# Sisyphus.net
KiCad netlist of a schematic drawn in EasyEDA Pro
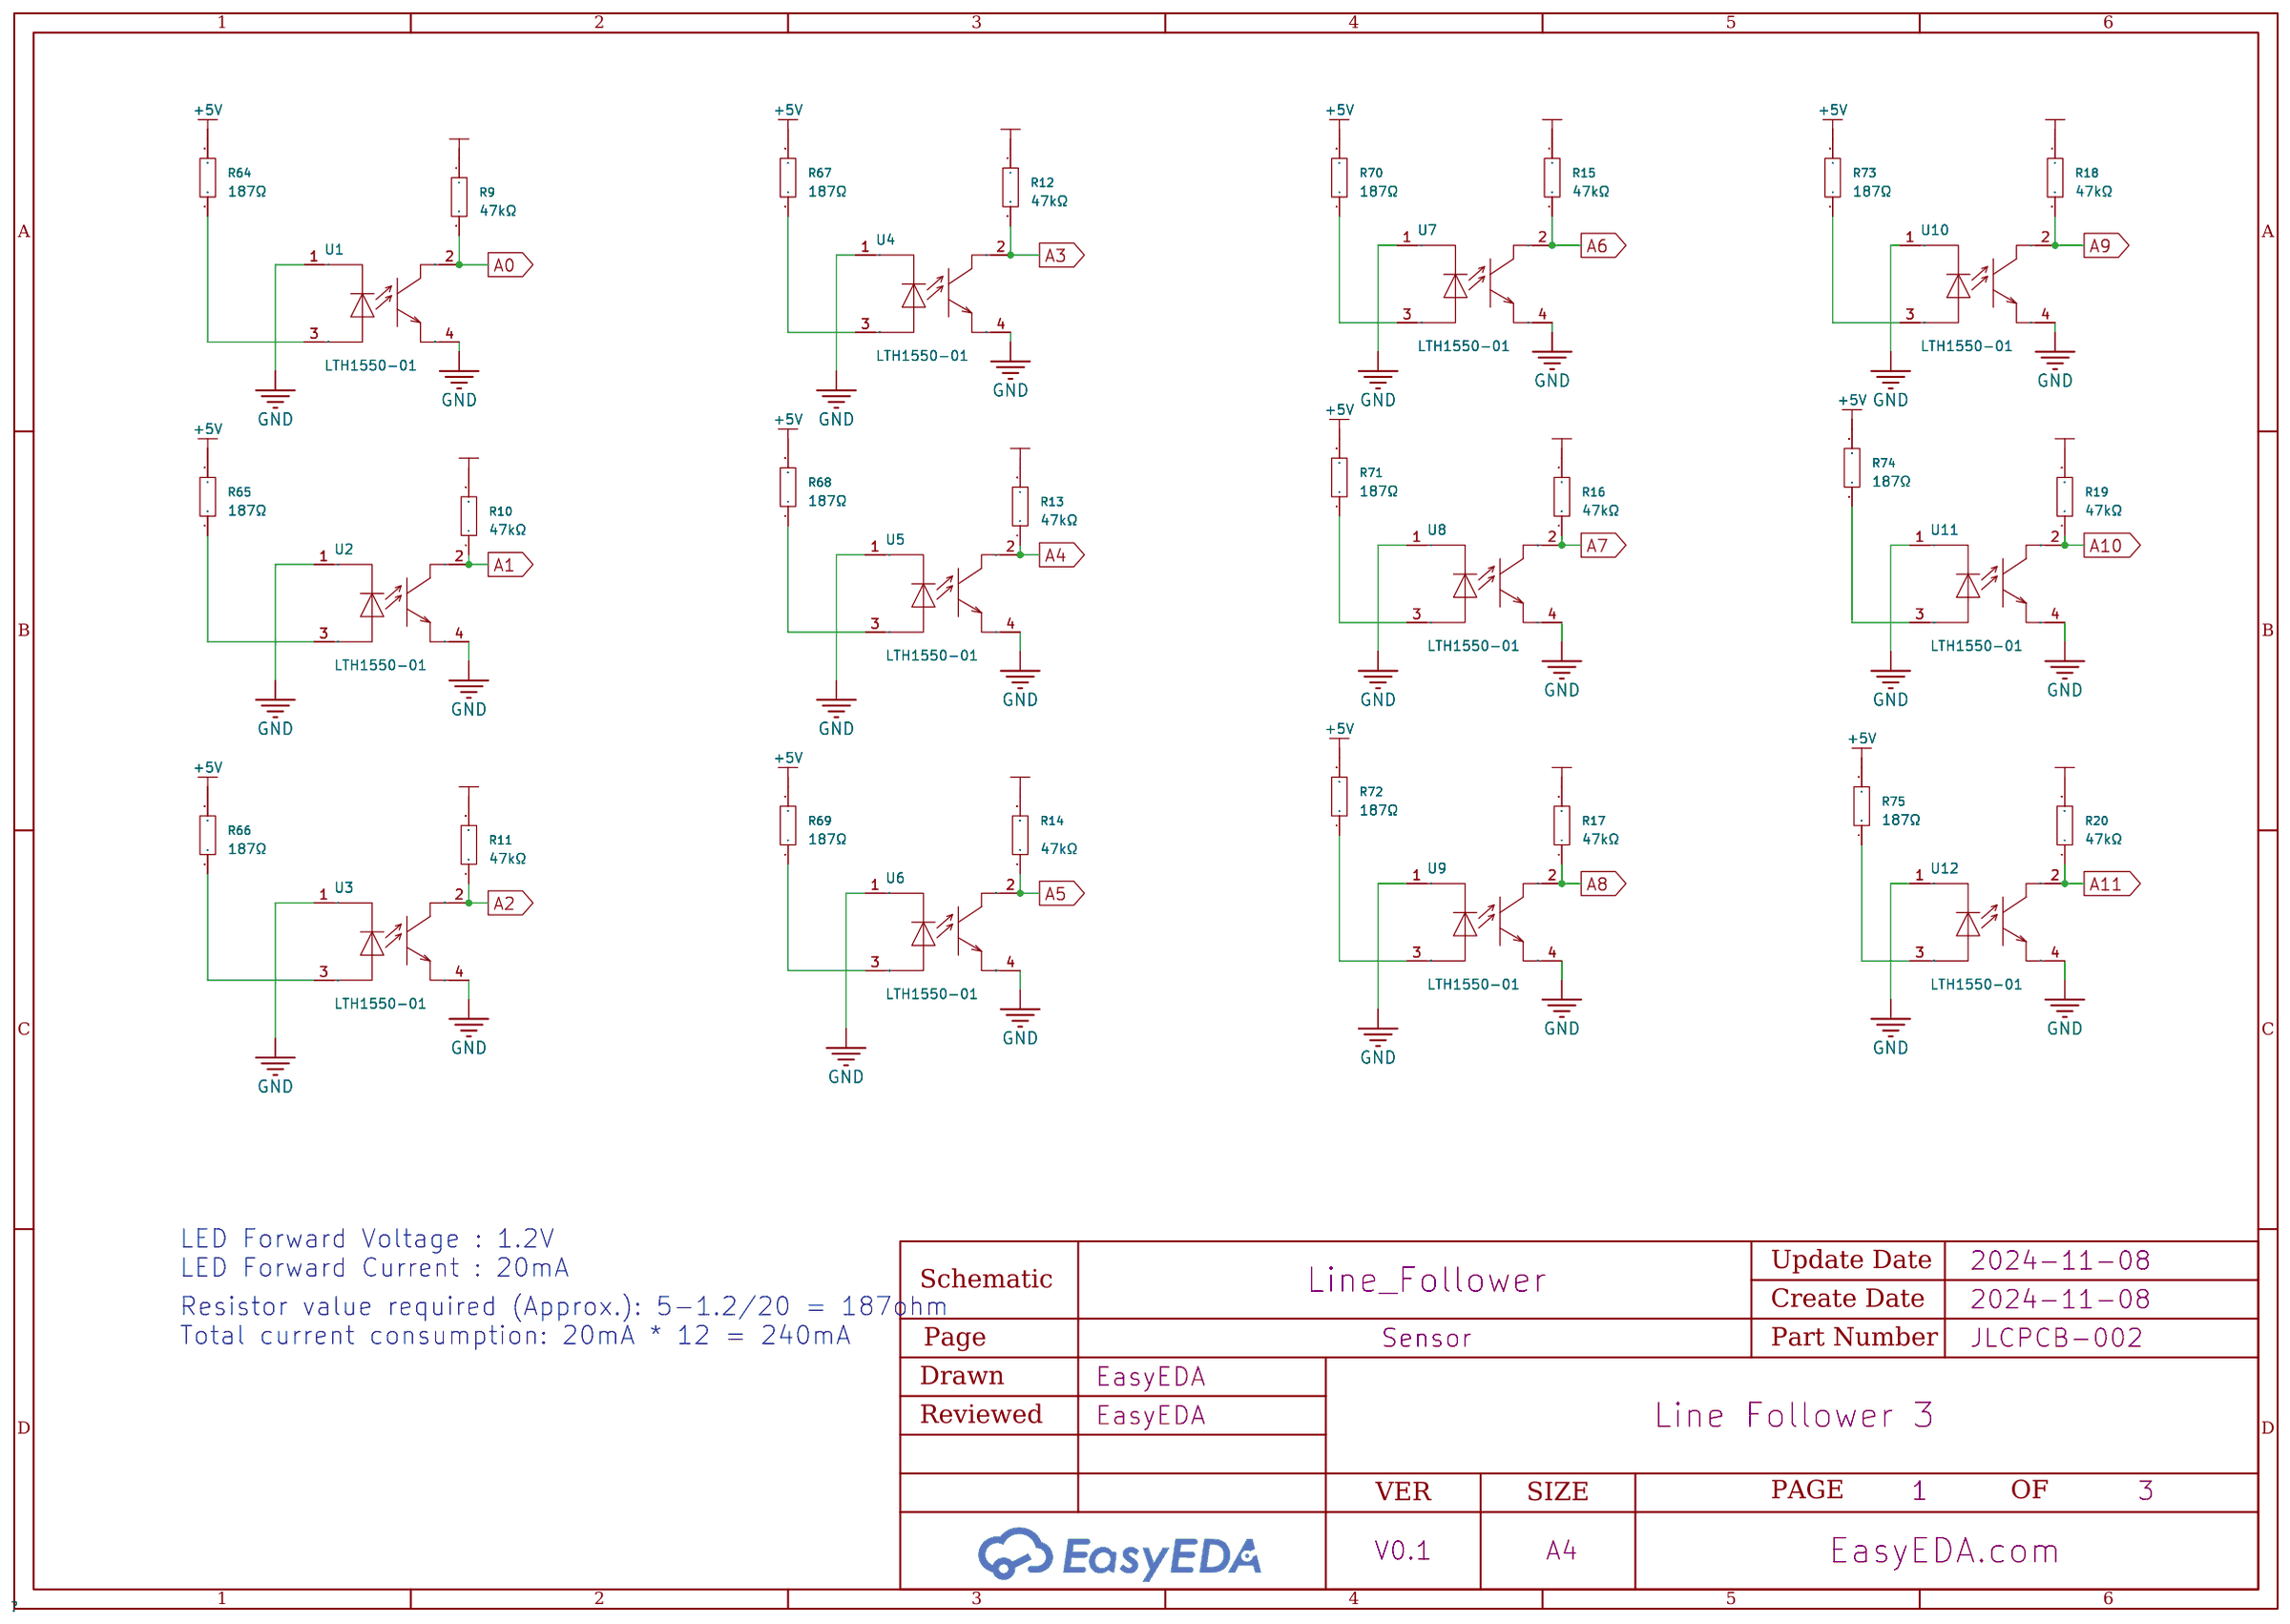
[diagram p0: Sensor]
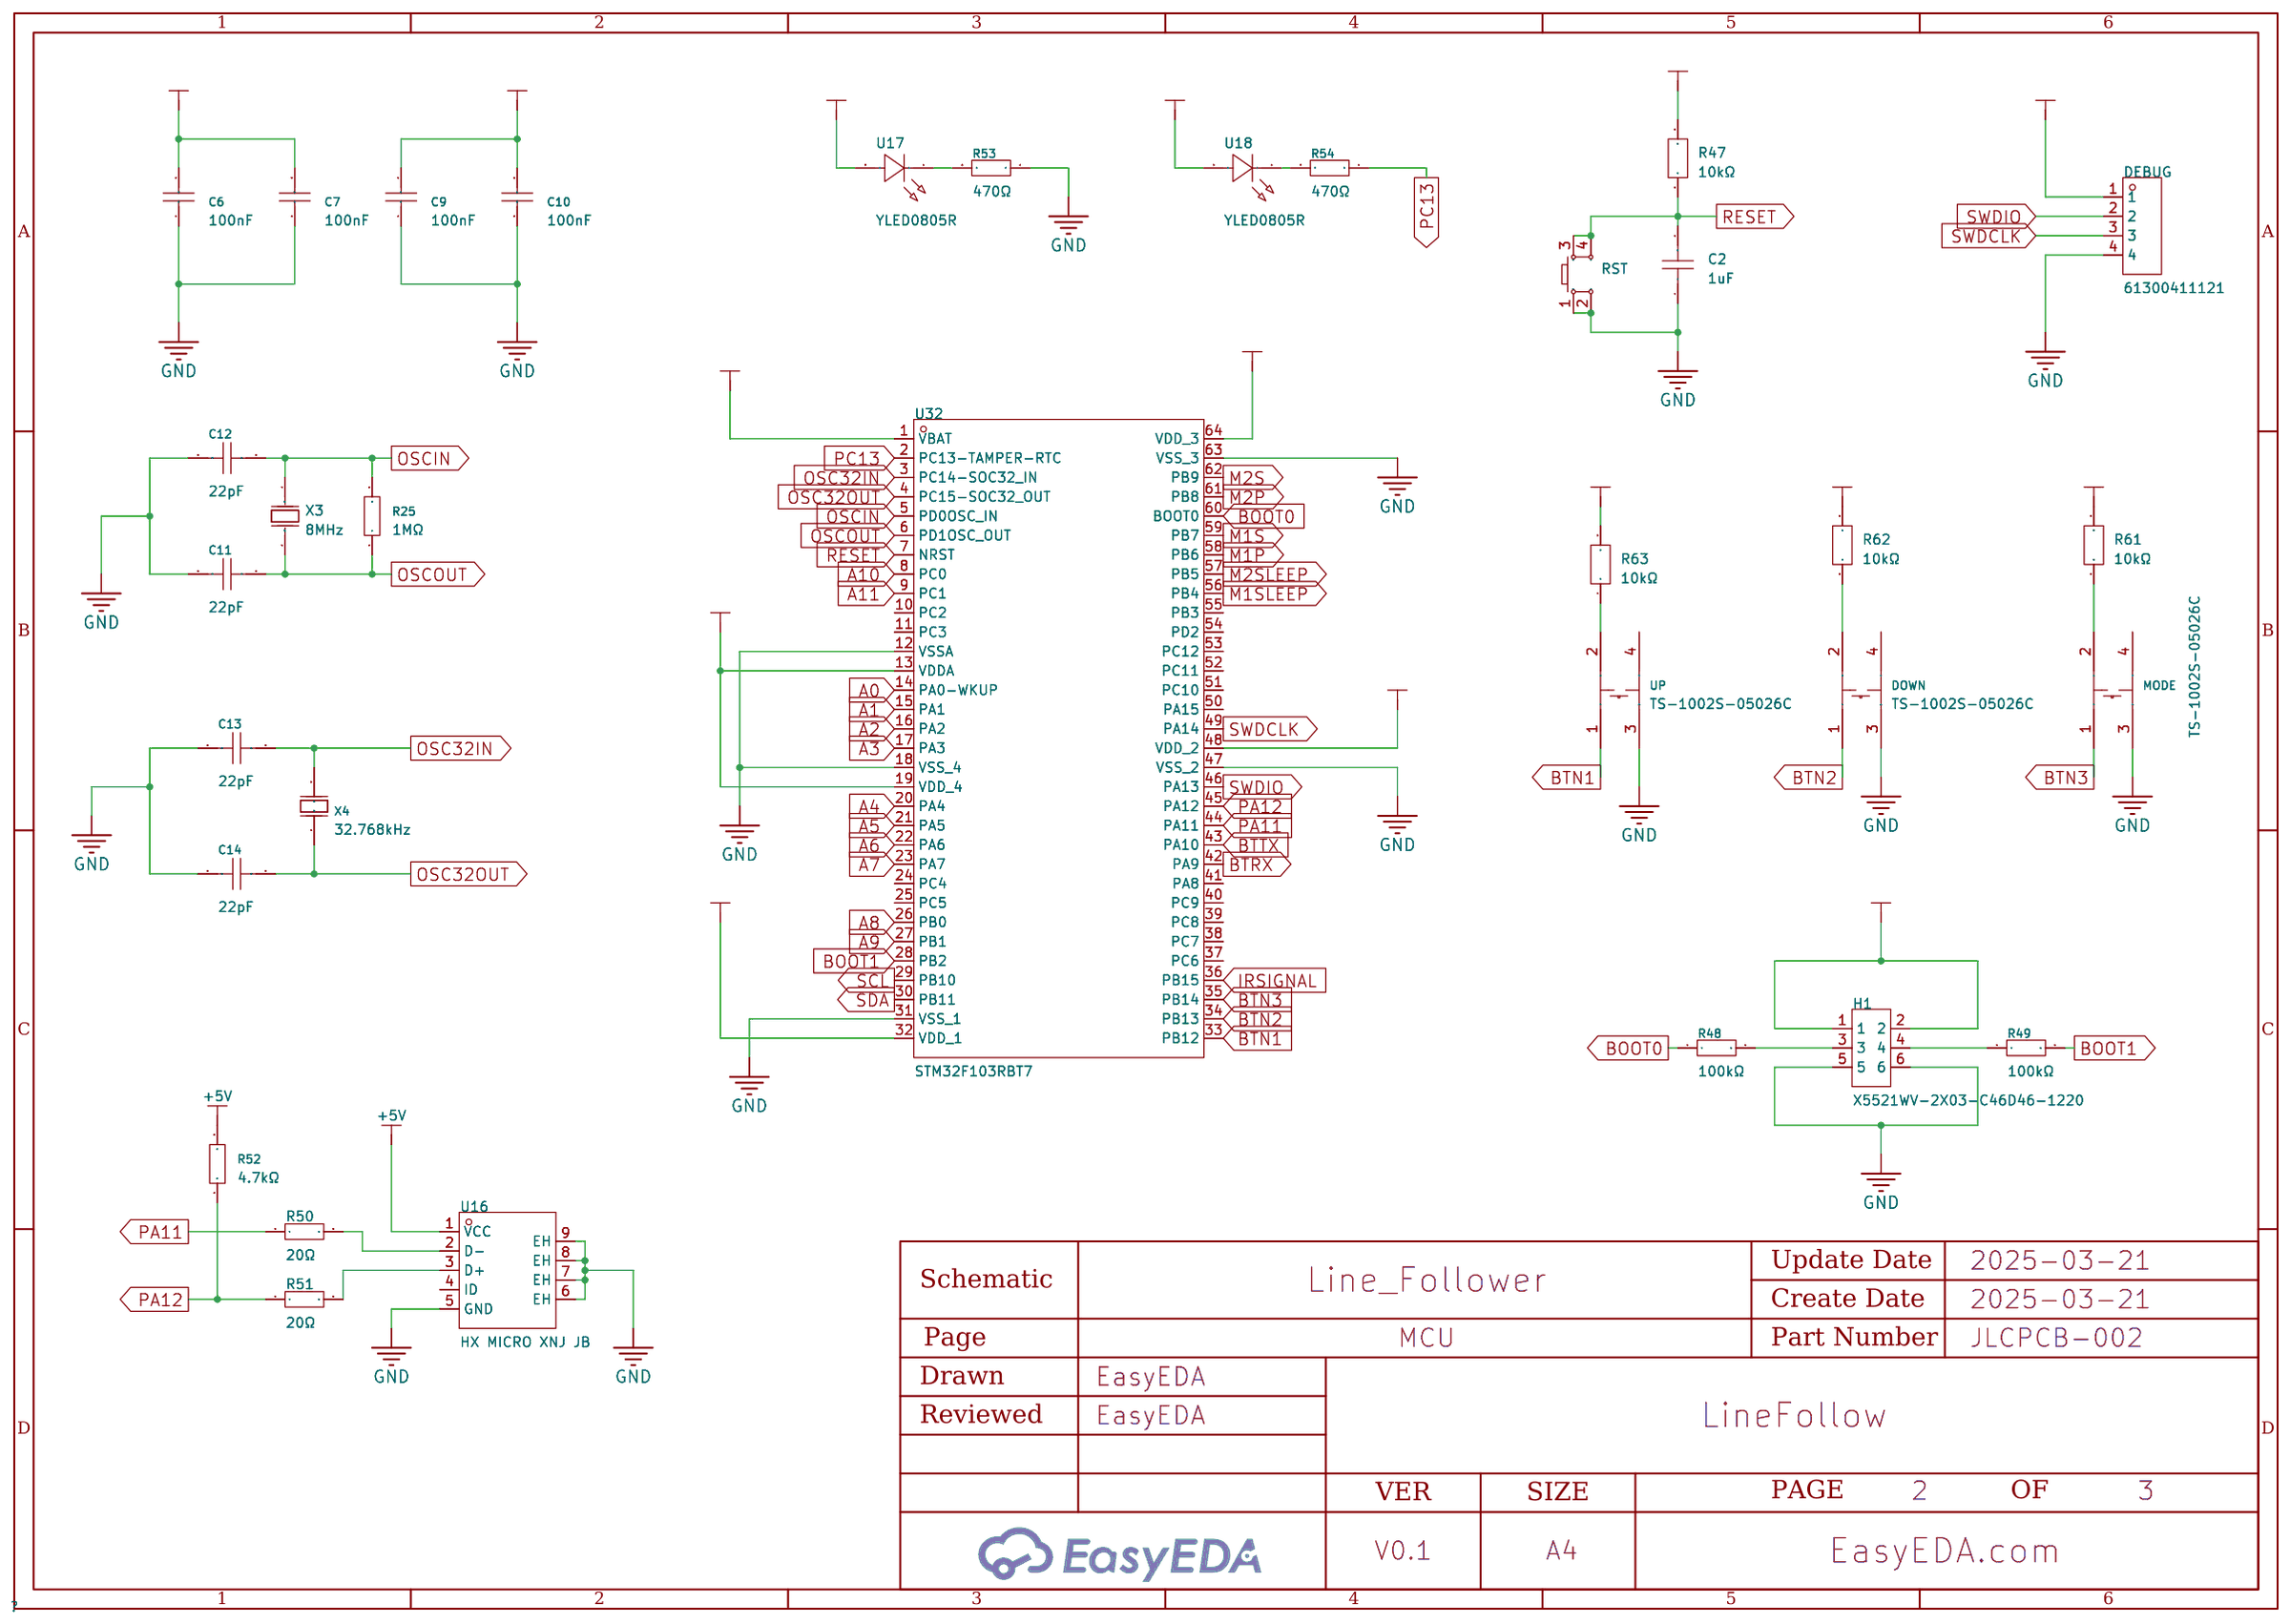
[diagram p1: MCU]
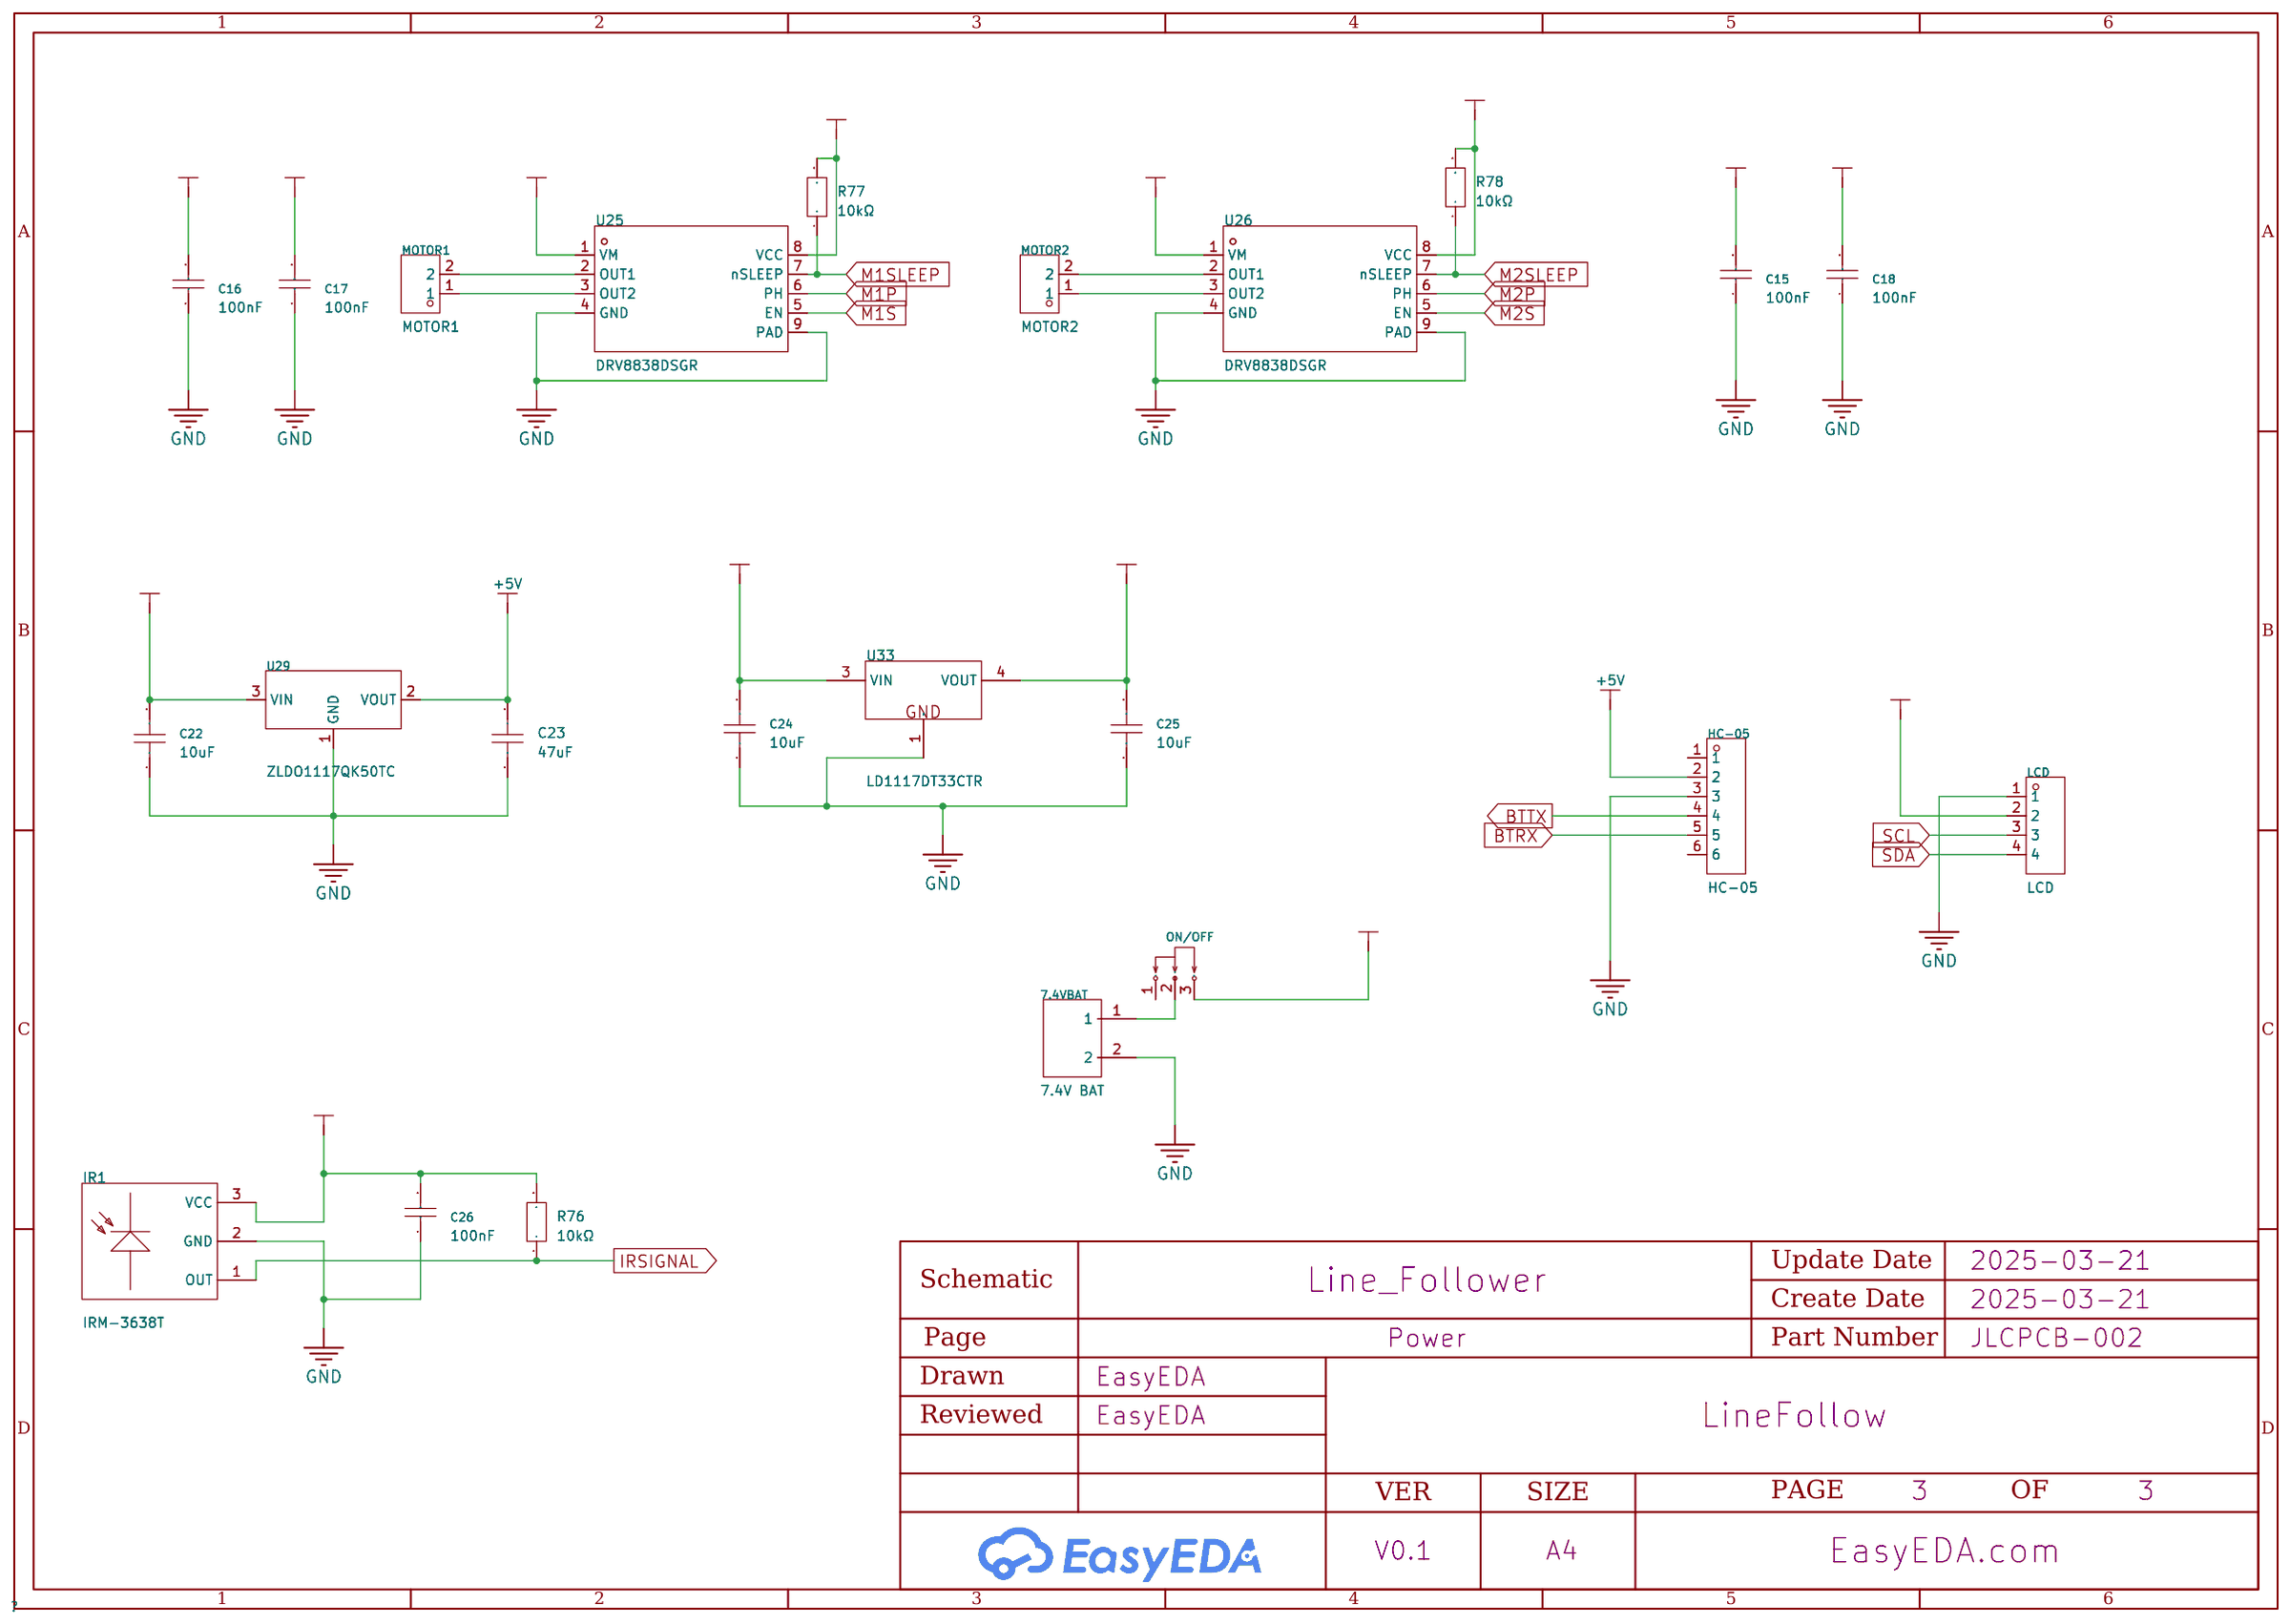
[diagram p2: Power]

(export (version "E")
  (design (tool "Eeschema 10.0.6"))
  (components
    (comp (ref "R9")
      (value "47kΩ")
      (footprint "easyedapro:R0805")
      (fields
        (field (name "Manufacturer Part") "0805W8F4702T5E")
        (field (name "Manufacturer") "UNI-ROYAL(厚声)")
      )
      (libsource (lib "easyedapro") (part "0805W8F4702T5E"))
    )
    (comp (ref "R10")
      (value "47kΩ")
      (footprint "easyedapro:R0805")
      (fields
        (field (name "Manufacturer Part") "0805W8F4702T5E")
        (field (name "Manufacturer") "UNI-ROYAL(厚声)")
      )
      (libsource (lib "easyedapro") (part "0805W8F4702T5E"))
    )
    (comp (ref "R11")
      (value "47kΩ")
      (footprint "easyedapro:R0805")
      (fields
        (field (name "Manufacturer Part") "0805W8F4702T5E")
        (field (name "Manufacturer") "UNI-ROYAL(厚声)")
      )
      (libsource (lib "easyedapro") (part "0805W8F4702T5E"))
    )
    (comp (ref "R12")
      (value "47kΩ")
      (footprint "easyedapro:R0805")
      (fields
        (field (name "Manufacturer Part") "0805W8F4702T5E")
        (field (name "Manufacturer") "UNI-ROYAL(厚声)")
      )
      (libsource (lib "easyedapro") (part "0805W8F4702T5E"))
    )
    (comp (ref "R13")
      (value "47kΩ")
      (footprint "easyedapro:R0805")
      (fields
        (field (name "Manufacturer Part") "0805W8F4702T5E")
        (field (name "Manufacturer") "UNI-ROYAL(厚声)")
      )
      (libsource (lib "easyedapro") (part "0805W8F4702T5E"))
    )
    (comp (ref "R14")
      (value "47kΩ")
      (footprint "easyedapro:R0805")
      (fields
        (field (name "Manufacturer Part") "0805W8F4702T5E")
        (field (name "Manufacturer") "UNI-ROYAL(厚声)")
      )
      (libsource (lib "easyedapro") (part "0805W8F4702T5E"))
    )
    (comp (ref "R15")
      (value "47kΩ")
      (footprint "easyedapro:R0805")
      (fields
        (field (name "Manufacturer Part") "0805W8F4702T5E")
        (field (name "Manufacturer") "UNI-ROYAL(厚声)")
      )
      (libsource (lib "easyedapro") (part "0805W8F4702T5E"))
    )
    (comp (ref "R16")
      (value "47kΩ")
      (footprint "easyedapro:R0805")
      (fields
        (field (name "Manufacturer Part") "0805W8F4702T5E")
        (field (name "Manufacturer") "UNI-ROYAL(厚声)")
      )
      (libsource (lib "easyedapro") (part "0805W8F4702T5E"))
    )
    (comp (ref "R17")
      (value "47kΩ")
      (footprint "easyedapro:R0805")
      (fields
        (field (name "Manufacturer Part") "0805W8F4702T5E")
        (field (name "Manufacturer") "UNI-ROYAL(厚声)")
      )
      (libsource (lib "easyedapro") (part "0805W8F4702T5E"))
    )
    (comp (ref "R18")
      (value "47kΩ")
      (footprint "easyedapro:R0805")
      (fields
        (field (name "Manufacturer Part") "0805W8F4702T5E")
        (field (name "Manufacturer") "UNI-ROYAL(厚声)")
      )
      (libsource (lib "easyedapro") (part "0805W8F4702T5E"))
    )
    (comp (ref "R19")
      (value "47kΩ")
      (footprint "easyedapro:R0805")
      (fields
        (field (name "Manufacturer Part") "0805W8F4702T5E")
        (field (name "Manufacturer") "UNI-ROYAL(厚声)")
      )
      (libsource (lib "easyedapro") (part "0805W8F4702T5E"))
    )
    (comp (ref "R20")
      (value "47kΩ")
      (footprint "easyedapro:R0805")
      (fields
        (field (name "Manufacturer Part") "0805W8F4702T5E")
        (field (name "Manufacturer") "UNI-ROYAL(厚声)")
      )
      (libsource (lib "easyedapro") (part "0805W8F4702T5E"))
    )
    (comp (ref "R64")
      (value "187Ω")
      (footprint "easyedapro:R0805")
      (fields (field (name "Manufacturer Part") "RTT051870FTP") (field (name "Manufacturer") "RALEC(旺诠)"))
      (libsource (lib "easyedapro") (part "RTT051870FTP"))
    )
    (comp (ref "R65")
      (value "187Ω")
      (footprint "easyedapro:R0805")
      (fields (field (name "Manufacturer Part") "RTT051870FTP") (field (name "Manufacturer") "RALEC(旺诠)"))
      (libsource (lib "easyedapro") (part "RTT051870FTP"))
    )
    (comp (ref "R66")
      (value "187Ω")
      (footprint "easyedapro:R0805")
      (fields (field (name "Manufacturer Part") "RTT051870FTP") (field (name "Manufacturer") "RALEC(旺诠)"))
      (libsource (lib "easyedapro") (part "RTT051870FTP"))
    )
    (comp (ref "R67")
      (value "187Ω")
      (footprint "easyedapro:R0805")
      (fields (field (name "Manufacturer Part") "RTT051870FTP") (field (name "Manufacturer") "RALEC(旺诠)"))
      (libsource (lib "easyedapro") (part "RTT051870FTP"))
    )
    (comp (ref "R68")
      (value "187Ω")
      (footprint "easyedapro:R0805")
      (fields (field (name "Manufacturer Part") "RTT051870FTP") (field (name "Manufacturer") "RALEC(旺诠)"))
      (libsource (lib "easyedapro") (part "RTT051870FTP"))
    )
    (comp (ref "R69")
      (value "187Ω")
      (footprint "easyedapro:R0805")
      (fields (field (name "Manufacturer Part") "RTT051870FTP") (field (name "Manufacturer") "RALEC(旺诠)"))
      (libsource (lib "easyedapro") (part "RTT051870FTP"))
    )
    (comp (ref "R70")
      (value "187Ω")
      (footprint "easyedapro:R0805")
      (fields (field (name "Manufacturer Part") "RTT051870FTP") (field (name "Manufacturer") "RALEC(旺诠)"))
      (libsource (lib "easyedapro") (part "RTT051870FTP"))
    )
    (comp (ref "R71")
      (value "187Ω")
      (footprint "easyedapro:R0805")
      (fields (field (name "Manufacturer Part") "RTT051870FTP") (field (name "Manufacturer") "RALEC(旺诠)"))
      (libsource (lib "easyedapro") (part "RTT051870FTP"))
    )
    (comp (ref "R72")
      (value "187Ω")
      (footprint "easyedapro:R0805")
      (fields (field (name "Manufacturer Part") "RTT051870FTP") (field (name "Manufacturer") "RALEC(旺诠)"))
      (libsource (lib "easyedapro") (part "RTT051870FTP"))
    )
    (comp (ref "R73")
      (value "187Ω")
      (footprint "easyedapro:R0805")
      (fields (field (name "Manufacturer Part") "RTT051870FTP") (field (name "Manufacturer") "RALEC(旺诠)"))
      (libsource (lib "easyedapro") (part "RTT051870FTP"))
    )
    (comp (ref "R74")
      (value "187Ω")
      (footprint "easyedapro:R0805")
      (fields (field (name "Manufacturer Part") "RTT051870FTP") (field (name "Manufacturer") "RALEC(旺诠)"))
      (libsource (lib "easyedapro") (part "RTT051870FTP"))
    )
    (comp (ref "R75")
      (value "187Ω")
      (footprint "easyedapro:R0805")
      (fields (field (name "Manufacturer Part") "RTT051870FTP") (field (name "Manufacturer") "RALEC(旺诠)"))
      (libsource (lib "easyedapro") (part "RTT051870FTP"))
    )
    (comp (ref "U1")
      (value "LTH1550-01")
      (footprint "easyedapro:OPTO-TH_4P-L8.7-W4.5-P4.10_LTH1550-01")
      (libsource (lib "easyedapro") (part "LTH1550-01"))
    )
    (comp (ref "U2")
      (value "LTH1550-01")
      (footprint "easyedapro:OPTO-TH_4P-L8.7-W4.5-P4.10_LTH1550-01")
      (libsource (lib "easyedapro") (part "LTH1550-01"))
    )
    (comp (ref "U3")
      (value "LTH1550-01")
      (footprint "easyedapro:OPTO-TH_4P-L8.7-W4.5-P4.10_LTH1550-01")
      (libsource (lib "easyedapro") (part "LTH1550-01"))
    )
    (comp (ref "U4")
      (value "LTH1550-01")
      (footprint "easyedapro:OPTO-TH_4P-L8.7-W4.5-P4.10_LTH1550-01")
      (libsource (lib "easyedapro") (part "LTH1550-01"))
    )
    (comp (ref "U5")
      (value "LTH1550-01")
      (footprint "easyedapro:OPTO-TH_4P-L8.7-W4.5-P4.10_LTH1550-01")
      (libsource (lib "easyedapro") (part "LTH1550-01"))
    )
    (comp (ref "U6")
      (value "LTH1550-01")
      (footprint "easyedapro:OPTO-TH_4P-L8.7-W4.5-P4.10_LTH1550-01")
      (libsource (lib "easyedapro") (part "LTH1550-01"))
    )
    (comp (ref "U7")
      (value "LTH1550-01")
      (footprint "easyedapro:OPTO-TH_4P-L8.7-W4.5-P4.10_LTH1550-01")
      (libsource (lib "easyedapro") (part "LTH1550-01"))
    )
    (comp (ref "U8")
      (value "LTH1550-01")
      (footprint "easyedapro:OPTO-TH_4P-L8.7-W4.5-P4.10_LTH1550-01")
      (libsource (lib "easyedapro") (part "LTH1550-01"))
    )
    (comp (ref "U9")
      (value "LTH1550-01")
      (footprint "easyedapro:OPTO-TH_4P-L8.7-W4.5-P4.10_LTH1550-01")
      (libsource (lib "easyedapro") (part "LTH1550-01"))
    )
    (comp (ref "U10")
      (value "LTH1550-01")
      (footprint "easyedapro:OPTO-TH_4P-L8.7-W4.5-P4.10_LTH1550-01")
      (libsource (lib "easyedapro") (part "LTH1550-01"))
    )
    (comp (ref "U11")
      (value "LTH1550-01")
      (footprint "easyedapro:OPTO-TH_4P-L8.7-W4.5-P4.10_LTH1550-01")
      (libsource (lib "easyedapro") (part "LTH1550-01"))
    )
    (comp (ref "U12")
      (value "LTH1550-01")
      (footprint "easyedapro:OPTO-TH_4P-L8.7-W4.5-P4.10_LTH1550-01")
      (libsource (lib "easyedapro") (part "LTH1550-01"))
    )
    (comp (ref "C2")
      (value "1uF")
      (footprint "easyedapro:C1206")
      (fields
        (field (name "Manufacturer Part") "CL31B105KBHNNNE")
        (field (name "Manufacturer") "SAMSUNG(三星)")
      )
      (libsource (lib "easyedapro") (part "CL31B105KBHNNNE"))
    )
    (comp (ref "C6")
      (value "100nF")
      (footprint "easyedapro:C1206")
      (fields
        (field (name "Manufacturer Part") "CL31B104KBCNNNC")
        (field (name "Manufacturer") "SAMSUNG(三星)")
      )
      (libsource (lib "easyedapro") (part "CL31B104KBCNNNC"))
    )
    (comp (ref "C7")
      (value "100nF")
      (footprint "easyedapro:C1206")
      (fields
        (field (name "Manufacturer Part") "CL31B104KBCNNNC")
        (field (name "Manufacturer") "SAMSUNG(三星)")
      )
      (libsource (lib "easyedapro") (part "CL31B104KBCNNNC"))
    )
    (comp (ref "C9")
      (value "100nF")
      (footprint "easyedapro:C1206")
      (fields
        (field (name "Manufacturer Part") "CL31B104KBCNNNC")
        (field (name "Manufacturer") "SAMSUNG(三星)")
      )
      (libsource (lib "easyedapro") (part "CL31B104KBCNNNC"))
    )
    (comp (ref "C10")
      (value "100nF")
      (footprint "easyedapro:C1206")
      (fields
        (field (name "Manufacturer Part") "CL31B104KBCNNNC")
        (field (name "Manufacturer") "SAMSUNG(三星)")
      )
      (libsource (lib "easyedapro") (part "CL31B104KBCNNNC"))
    )
    (comp (ref "C11")
      (value "22pF")
      (footprint "easyedapro:C0805")
      (fields
        (field (name "Manufacturer Part") "TCC0805COG220J500BT")
        (field (name "Manufacturer") "CCTC(三环)")
      )
      (libsource (lib "easyedapro") (part "TCC0805COG220J500BT"))
    )
    (comp (ref "C12")
      (value "22pF")
      (footprint "easyedapro:C0805")
      (fields
        (field (name "Manufacturer Part") "TCC0805COG220J500BT")
        (field (name "Manufacturer") "CCTC(三环)")
      )
      (libsource (lib "easyedapro") (part "TCC0805COG220J500BT"))
    )
    (comp (ref "C13")
      (value "22pF")
      (footprint "easyedapro:C0805")
      (fields
        (field (name "Manufacturer Part") "TCC0805COG220J500BT")
        (field (name "Manufacturer") "CCTC(三环)")
      )
      (libsource (lib "easyedapro") (part "TCC0805COG220J500BT"))
    )
    (comp (ref "C14")
      (value "22pF")
      (footprint "easyedapro:C0805")
      (fields
        (field (name "Manufacturer Part") "TCC0805COG220J500BT")
        (field (name "Manufacturer") "CCTC(三环)")
      )
      (libsource (lib "easyedapro") (part "TCC0805COG220J500BT"))
    )
    (comp (ref "DEBUG")
      (value "61300411121")
      (footprint "easyedapro:HDR-TH_4P-P2.54-V-M-1")
      (fields (field (name "Manufacturer") "Wurth(伍尔特)"))
      (libsource (lib "easyedapro") (part "61300411121"))
    )
    (comp (ref "DOWN")
      (value "TS-1002S-05026C")
      (footprint "easyedapro:KEY-SMD_4P-L6.0-W6.0-P4.50-LS9.0")
      (fields (field (name "Manufacturer") "XUNPU(讯普)"))
      (libsource (lib "easyedapro") (part "TS-1002S-05026C"))
    )
    (comp (ref "H1")
      (value "X5521WV-2X03-C46D46-1220")
      (footprint "easyedapro:HDR-TH_6P-P2.54-V-M-R2-C3-S2.54-3")
      (fields (field (name "Manufacturer") "XKB Connection(中国星坤)"))
      (libsource (lib "easyedapro") (part "X5521WV-2X03-C46D46-1220"))
    )
    (comp (ref "MODE")
      (value "TS-1002S-05026C")
      (footprint "easyedapro:KEY-SMD_4P-L6.0-W6.0-P4.50-LS9.0")
      (fields (field (name "Manufacturer") "XUNPU(讯普)"))
      (libsource (lib "easyedapro") (part "TS-1002S-05026C"))
    )
    (comp (ref "R25")
      (value "1MΩ")
      (footprint "easyedapro:R1206")
      (fields
        (field (name "Manufacturer Part") "1206W4F1004T5E")
        (field (name "Manufacturer") "UNI-ROYAL(厚声)")
      )
      (libsource (lib "easyedapro") (part "1206W4F1004T5E"))
    )
    (comp (ref "R47")
      (value "10kΩ")
      (footprint "easyedapro:R0805")
      (fields (field (name "Manufacturer Part") "FRC0805J103TS") (field (name "Manufacturer") "FOJAN(富捷)"))
      (libsource (lib "easyedapro") (part "FRC0805J103TS"))
    )
    (comp (ref "R48")
      (value "100kΩ")
      (footprint "easyedapro:R0805")
      (fields
        (field (name "Manufacturer Part") "0805W8F1003T5E")
        (field (name "Manufacturer") "UNI-ROYAL(厚声)")
      )
      (libsource (lib "easyedapro") (part "0805W8F1003T5E_C149504"))
    )
    (comp (ref "R49")
      (value "100kΩ")
      (footprint "easyedapro:R0805")
      (fields
        (field (name "Manufacturer Part") "0805W8F1003T5E")
        (field (name "Manufacturer") "UNI-ROYAL(厚声)")
      )
      (libsource (lib "easyedapro") (part "0805W8F1003T5E_C149504"))
    )
    (comp (ref "R50")
      (value "20Ω")
      (footprint "easyedapro:R0805")
      (fields (field (name "Manufacturer Part") "RS-05K20R0FT") (field (name "Manufacturer") "FH(风华)"))
      (libsource (lib "easyedapro") (part "RS-05K20R0FT"))
    )
    (comp (ref "R51")
      (value "20Ω")
      (footprint "easyedapro:R0805")
      (fields (field (name "Manufacturer Part") "RS-05K20R0FT") (field (name "Manufacturer") "FH(风华)"))
      (libsource (lib "easyedapro") (part "RS-05K20R0FT"))
    )
    (comp (ref "R52")
      (value "4.7kΩ")
      (footprint "easyedapro:R0805")
      (fields
        (field (name "Manufacturer Part") "0805W8F4701T5E")
        (field (name "Manufacturer") "UNI-ROYAL(厚声)")
      )
      (libsource (lib "easyedapro") (part "0805W8F4701T5E"))
    )
    (comp (ref "R53")
      (value "470Ω")
      (footprint "easyedapro:R0805")
      (fields
        (field (name "Manufacturer Part") "0805W8F4700T5E")
        (field (name "Manufacturer") "UNI-ROYAL(厚声)")
      )
      (libsource (lib "easyedapro") (part "0805W8F4700T5E"))
    )
    (comp (ref "R54")
      (value "470Ω")
      (footprint "easyedapro:R0805")
      (fields
        (field (name "Manufacturer Part") "0805W8F4700T5E")
        (field (name "Manufacturer") "UNI-ROYAL(厚声)")
      )
      (libsource (lib "easyedapro") (part "0805W8F4700T5E"))
    )
    (comp (ref "R61")
      (value "10kΩ")
      (footprint "easyedapro:R0805")
      (fields (field (name "Manufacturer Part") "FRC0805J103TS") (field (name "Manufacturer") "FOJAN(富捷)"))
      (libsource (lib "easyedapro") (part "FRC0805J103TS"))
    )
    (comp (ref "R62")
      (value "10kΩ")
      (footprint "easyedapro:R0805")
      (fields (field (name "Manufacturer Part") "FRC0805J103TS") (field (name "Manufacturer") "FOJAN(富捷)"))
      (libsource (lib "easyedapro") (part "FRC0805J103TS"))
    )
    (comp (ref "R63")
      (value "10kΩ")
      (footprint "easyedapro:R0805")
      (fields (field (name "Manufacturer Part") "FRC0805J103TS") (field (name "Manufacturer") "FOJAN(富捷)"))
      (libsource (lib "easyedapro") (part "FRC0805J103TS"))
    )
    (comp (ref "RST")
      (value "~")
      (footprint "easyedapro:SW-SMD_4P-L6.0-W6.0-P4.50-LS9.0-2")
      (libsource (lib "easyedapro") (part "轻触按键"))
    )
    (comp (ref "U16")
      (value "HX MICRO XNJ JB")
      (footprint "easyedapro:MICRO-USB-SMD_MICRONJ5P-1.0-1.25")
      (description "Connector Type:Micro-B Gender:Female")
      (fields (field (name "Manufacturer") "hanxia(韩下)"))
      (libsource (lib "easyedapro") (part "HX MICRO XNJ JB"))
    )
    (comp (ref "U17")
      (value "YLED0805R")
      (footprint "easyedapro:LED0805-RD")
      (fields (field (name "Manufacturer") "YONGYUTAI(永裕泰)"))
      (libsource (lib "easyedapro") (part "YLED0805R"))
    )
    (comp (ref "U18")
      (value "YLED0805R")
      (footprint "easyedapro:LED0805-RD")
      (fields (field (name "Manufacturer") "YONGYUTAI(永裕泰)"))
      (libsource (lib "easyedapro") (part "YLED0805R"))
    )
    (comp (ref "U32")
      (value "STM32F103RBT7")
      (footprint "easyedapro:LQFP-64_L10.0-W10.0-P0.50-LS12.0-BL")
      (fields (field (name "Manufacturer") "ST(意法半导体)"))
      (libsource (lib "easyedapro") (part "STM32F103RBT7"))
    )
    (comp (ref "UP")
      (value "TS-1002S-05026C")
      (footprint "easyedapro:KEY-SMD_4P-L6.0-W6.0-P4.50-LS9.0")
      (fields (field (name "Manufacturer") "XUNPU(讯普)"))
      (libsource (lib "easyedapro") (part "TS-1002S-05026C"))
    )
    (comp (ref "X3")
      (value "8MHz")
      (footprint "easyedapro:CRYSTAL-SMD_L11.5-W4.8-LS12.7")
      (fields (field (name "Manufacturer Part") "X49SM8MSD2SC") (field (name "Manufacturer") "YXC(扬兴晶振)"))
      (libsource (lib "easyedapro") (part "X49SM8MSD2SC"))
    )
    (comp (ref "X4")
      (value "32.768kHz")
      (footprint "easyedapro:OSC-SMD_2P-L3.2-W1.5")
      (fields (field (name "Manufacturer Part") "ABS07-32.768KHZ-T") (field (name "Manufacturer") "ABRACON"))
      (libsource (lib "easyedapro") (part "ABS07-32.768KHZ-T"))
    )
    (comp (ref "7.4VBAT")
      (value "7.4V BAT")
      (footprint "easyedapro:CONN-TH_WJ126V-5.0-2P")
      (fields (field (name "Manufacturer") "KANGNEX(康奈克斯电气)"))
      (libsource (lib "easyedapro") (part "WJ126V-5.0-2P"))
    )
    (comp (ref "C15")
      (value "100nF")
      (footprint "easyedapro:C1206")
      (fields
        (field (name "Manufacturer Part") "CL31B104KBCNNNC")
        (field (name "Manufacturer") "SAMSUNG(三星)")
      )
      (libsource (lib "easyedapro") (part "CL31B104KBCNNNC"))
    )
    (comp (ref "C16")
      (value "100nF")
      (footprint "easyedapro:C1206")
      (fields
        (field (name "Manufacturer Part") "CL31B104KBCNNNC")
        (field (name "Manufacturer") "SAMSUNG(三星)")
      )
      (libsource (lib "easyedapro") (part "CL31B104KBCNNNC"))
    )
    (comp (ref "C17")
      (value "100nF")
      (footprint "easyedapro:C1206")
      (fields
        (field (name "Manufacturer Part") "CL31B104KBCNNNC")
        (field (name "Manufacturer") "SAMSUNG(三星)")
      )
      (libsource (lib "easyedapro") (part "CL31B104KBCNNNC"))
    )
    (comp (ref "C18")
      (value "100nF")
      (footprint "easyedapro:C1206")
      (fields
        (field (name "Manufacturer Part") "CL31B104KBCNNNC")
        (field (name "Manufacturer") "SAMSUNG(三星)")
      )
      (libsource (lib "easyedapro") (part "CL31B104KBCNNNC"))
    )
    (comp (ref "C22")
      (value "10uF")
      (footprint "easyedapro:C0805")
      (fields
        (field (name "Manufacturer Part") "GRM21BR61E106KA73L")
        (field (name "Manufacturer") "muRata(村田)")
      )
      (libsource (lib "easyedapro") (part "GRM21BR61E106KA73L"))
    )
    (comp (ref "C23")
      (value "47uF")
      (footprint "easyedapro:C1206")
      (fields
        (field (name "Manufacturer Part") "GRM31CR61E476ME44L")
        (field (name "Manufacturer") "muRata(村田)")
      )
      (libsource (lib "easyedapro") (part "GRM31CR61E476ME44L"))
    )
    (comp (ref "C24")
      (value "10uF")
      (footprint "easyedapro:C0805")
      (fields
        (field (name "Manufacturer Part") "GRM21BR61E106KA73L")
        (field (name "Manufacturer") "muRata(村田)")
      )
      (libsource (lib "easyedapro") (part "GRM21BR61E106KA73L"))
    )
    (comp (ref "C25")
      (value "10uF")
      (footprint "easyedapro:C0805")
      (fields
        (field (name "Manufacturer Part") "GRM21BR61E106KA73L")
        (field (name "Manufacturer") "muRata(村田)")
      )
      (libsource (lib "easyedapro") (part "GRM21BR61E106KA73L"))
    )
    (comp (ref "C26")
      (value "100nF")
      (footprint "easyedapro:C1206")
      (fields
        (field (name "Manufacturer Part") "CL31B104KBCNNNC")
        (field (name "Manufacturer") "SAMSUNG(三星)")
      )
      (libsource (lib "easyedapro") (part "CL31B104KBCNNNC"))
    )
    (comp (ref "HC-05")
      (value "HC-05")
      (footprint "easyedapro:HDR-TH_6P-P2.54-V-F")
      (fields (field (name "Manufacturer") "BOOMELE(博穆精密)"))
      (libsource (lib "easyedapro") (part "Header-Female-2.54_1x6"))
    )
    (comp (ref "IR1")
      (value "IRM-3638T")
      (footprint "easyedapro:OPTO-TH_IRM-3638T")
      (fields (field (name "Manufacturer") "EVERLIGHT(亿光)"))
      (libsource (lib "easyedapro") (part "IRM-3638T"))
    )
    (comp (ref "LCD")
      (value "LCD")
      (footprint "easyedapro:HDR-TH_4P-P2.54-V-F")
      (fields (field (name "Manufacturer") "BOOMELE(博穆精密)"))
      (libsource (lib "easyedapro") (part "2.54-1*4P母"))
    )
    (comp (ref "MOTOR1")
      (value "MOTOR1")
      (footprint "easyedapro:HDR-TH_2P-P2.54-V-M")
      (fields (field (name "Manufacturer") "XFCN(兴飞)"))
      (libsource (lib "easyedapro") (part "PZ254V-11-02P"))
    )
    (comp (ref "MOTOR2")
      (value "MOTOR2")
      (footprint "easyedapro:HDR-TH_2P-P2.54-V-M")
      (fields (field (name "Manufacturer") "XFCN(兴飞)"))
      (libsource (lib "easyedapro") (part "PZ254V-11-02P"))
    )
    (comp (ref "ON/OFF")
      (value "SS12D10G4 071")
      (footprint "easyedapro:SW-TH_SHOU-HAN_SS12D10G4")
      (fields (field (name "Manufacturer") "SHOU HAN(首韩)"))
      (libsource (lib "easyedapro") (part "SS12D10G4 071"))
    )
    (comp (ref "R76")
      (value "10kΩ")
      (footprint "easyedapro:R0805")
      (fields (field (name "Manufacturer Part") "FRC0805J103TS") (field (name "Manufacturer") "FOJAN(富捷)"))
      (libsource (lib "easyedapro") (part "FRC0805J103TS"))
    )
    (comp (ref "R77")
      (value "10kΩ")
      (footprint "easyedapro:R0805")
      (fields (field (name "Manufacturer Part") "FRC0805J103TS") (field (name "Manufacturer") "FOJAN(富捷)"))
      (libsource (lib "easyedapro") (part "FRC0805J103TS"))
    )
    (comp (ref "R78")
      (value "10kΩ")
      (footprint "easyedapro:R0805")
      (fields (field (name "Manufacturer Part") "FRC0805J103TS") (field (name "Manufacturer") "FOJAN(富捷)"))
      (libsource (lib "easyedapro") (part "FRC0805J103TS"))
    )
    (comp (ref "U25")
      (value "DRV8838DSGR")
      (footprint "easyedapro:WSON-8_L2.0-W2.0-P0.50-TL-EP")
      (fields (field (name "Manufacturer") "TI(德州仪器)"))
      (libsource (lib "easyedapro") (part "DRV8838DSGR"))
    )
    (comp (ref "U26")
      (value "DRV8838DSGR")
      (footprint "easyedapro:WSON-8_L2.0-W2.0-P0.50-TL-EP")
      (fields (field (name "Manufacturer") "TI(德州仪器)"))
      (libsource (lib "easyedapro") (part "DRV8838DSGR"))
    )
    (comp (ref "U29")
      (value "ZLDO1117QK50TC")
      (footprint "easyedapro:TO-252-3_L6.6-W6.1-P4.57-LS9.9-BR-CW")
      (fields (field (name "Manufacturer") "DIODES(美台)"))
      (libsource (lib "easyedapro") (part "ZLDO1117QK50TC"))
    )
    (comp (ref "U33")
      (value "LD1117DT33CTR")
      (footprint "easyedapro:TO-252-2_L6.5-W6.1-P4.58-LS10.0-TL")
      (fields (field (name "Manufacturer") "ST(意法半导体)"))
      (libsource (lib "easyedapro") (part "LD1117DT33CTR"))
    )
  )
  (nets
    (net (code "1") (name "+3.3V") (class "Default")
      (node (ref "C10") (pin "2") (pinfunction "2_2") (pintype "input"))
      (node (ref "C17") (pin "2") (pinfunction "2_2") (pintype "input"))
      (node (ref "C18") (pin "2") (pinfunction "2_2") (pintype "input"))
      (node (ref "C25") (pin "2") (pinfunction "2_2") (pintype "input"))
      (node (ref "C26") (pin "2") (pinfunction "2_2") (pintype "input"))
      (node (ref "C6") (pin "2") (pinfunction "2_2") (pintype "input"))
      (node (ref "C7") (pin "2") (pinfunction "2_2") (pintype "input"))
      (node (ref "C9") (pin "2") (pinfunction "2_2") (pintype "input"))
      (node (ref "DEBUG") (pin "1") (pinfunction "1_1") (pintype "unspecified"))
      (node (ref "H1") (pin "1") (pinfunction "1_1") (pintype "unspecified"))
      (node (ref "H1") (pin "2") (pinfunction "2_2") (pintype "unspecified"))
      (node (ref "IR1") (pin "3") (pinfunction "VCC_3") (pintype "input"))
      (node (ref "LCD") (pin "2") (pinfunction "2_2") (pintype "input"))
      (node (ref "R10") (pin "2") (pinfunction "2_2") (pintype "input"))
      (node (ref "R11") (pin "2") (pinfunction "2_2") (pintype "input"))
      (node (ref "R12") (pin "1") (pinfunction "1_1") (pintype "input"))
      (node (ref "R13") (pin "2") (pinfunction "2_2") (pintype "input"))
      (node (ref "R14") (pin "2") (pinfunction "2_2") (pintype "input"))
      (node (ref "R15") (pin "1") (pinfunction "1_1") (pintype "input"))
      (node (ref "R16") (pin "2") (pinfunction "2_2") (pintype "input"))
      (node (ref "R17") (pin "2") (pinfunction "2_2") (pintype "input"))
      (node (ref "R18") (pin "1") (pinfunction "1_1") (pintype "input"))
      (node (ref "R19") (pin "2") (pinfunction "2_2") (pintype "input"))
      (node (ref "R20") (pin "2") (pinfunction "2_2") (pintype "input"))
      (node (ref "R47") (pin "2") (pinfunction "2_2") (pintype "unspecified"))
      (node (ref "R61") (pin "2") (pinfunction "2_2") (pintype "unspecified"))
      (node (ref "R62") (pin "1") (pinfunction "1_1") (pintype "unspecified"))
      (node (ref "R63") (pin "2") (pinfunction "2_2") (pintype "unspecified"))
      (node (ref "R76") (pin "2") (pinfunction "2_2") (pintype "unspecified"))
      (node (ref "R77") (pin "2") (pinfunction "2_2") (pintype "unspecified"))
      (node (ref "R78") (pin "2") (pinfunction "2_2") (pintype "unspecified"))
      (node (ref "R9") (pin "1") (pinfunction "1_1") (pintype "input"))
      (node (ref "U17") (pin "2") (pinfunction "A_2") (pintype "unspecified"))
      (node (ref "U18") (pin "2") (pinfunction "A_2") (pintype "unspecified"))
      (node (ref "U25") (pin "8") (pinfunction "VCC_8") (pintype "unspecified"))
      (node (ref "U26") (pin "8") (pinfunction "VCC_8") (pintype "unspecified"))
      (node (ref "U32") (pin "1") (pinfunction "VBAT_1") (pintype "unspecified"))
      (node (ref "U32") (pin "13") (pinfunction "VDDA_13") (pintype "unspecified"))
      (node (ref "U32") (pin "19") (pinfunction "VDD_4_19") (pintype "unspecified"))
      (node (ref "U32") (pin "32") (pinfunction "VDD_1_32") (pintype "unspecified"))
      (node (ref "U32") (pin "48") (pinfunction "VDD_2_48") (pintype "unspecified"))
      (node (ref "U32") (pin "64") (pinfunction "VDD_3_64") (pintype "unspecified"))
      (node (ref "U33") (pin "4") (pinfunction "VOUT_4") (pintype "unspecified"))
    )
    (net (code "2") (name "+5V") (class "Default")
      (node (ref "C23") (pin "2") (pinfunction "2_2") (pintype "unspecified"))
      (node (ref "HC-05") (pin "2") (pinfunction "2_2") (pintype "input"))
      (node (ref "R52") (pin "2") (pinfunction "2_2") (pintype "input"))
      (node (ref "R64") (pin "2") (pinfunction "2_2") (pintype "input"))
      (node (ref "R65") (pin "2") (pinfunction "2_2") (pintype "input"))
      (node (ref "R66") (pin "2") (pinfunction "2_2") (pintype "input"))
      (node (ref "R67") (pin "2") (pinfunction "2_2") (pintype "input"))
      (node (ref "R68") (pin "2") (pinfunction "2_2") (pintype "input"))
      (node (ref "R69") (pin "2") (pinfunction "2_2") (pintype "input"))
      (node (ref "R70") (pin "2") (pinfunction "2_2") (pintype "input"))
      (node (ref "R71") (pin "2") (pinfunction "2_2") (pintype "input"))
      (node (ref "R72") (pin "2") (pinfunction "2_2") (pintype "input"))
      (node (ref "R73") (pin "2") (pinfunction "2_2") (pintype "input"))
      (node (ref "R74") (pin "2") (pinfunction "2_2") (pintype "input"))
      (node (ref "R75") (pin "2") (pinfunction "2_2") (pintype "input"))
      (node (ref "U16") (pin "1") (pinfunction "VCC_1") (pintype "unspecified"))
      (node (ref "U29") (pin "2") (pinfunction "VOUT_2") (pintype "input"))
    )
    (net (code "3") (name "+7.4V") (class "Default")
      (node (ref "C15") (pin "2") (pinfunction "2_2") (pintype "input"))
      (node (ref "C16") (pin "2") (pinfunction "2_2") (pintype "input"))
      (node (ref "C22") (pin "2") (pinfunction "2_2") (pintype "input"))
      (node (ref "C24") (pin "2") (pinfunction "2_2") (pintype "input"))
      (node (ref "ON/OFF") (pin "3") (pinfunction "3_3") (pintype "input"))
      (node (ref "U25") (pin "1") (pinfunction "VM_1") (pintype "unspecified"))
      (node (ref "U26") (pin "1") (pinfunction "VM_1") (pintype "unspecified"))
      (node (ref "U29") (pin "3") (pinfunction "VIN_3") (pintype "input"))
      (node (ref "U33") (pin "3") (pinfunction "VIN_3") (pintype "unspecified"))
    )
    (net (code "4") (name "A0") (class "Default")
      (node (ref "R9") (pin "2") (pinfunction "2_2") (pintype "input"))
      (node (ref "U1") (pin "2") (pinfunction "C_2") (pintype "unspecified"))
      (node (ref "U32") (pin "14") (pinfunction "PA0-WKUP_14") (pintype "unspecified"))
    )
    (net (code "5") (name "A1") (class "Default")
      (node (ref "R10") (pin "1") (pinfunction "1_1") (pintype "input"))
      (node (ref "U2") (pin "2") (pinfunction "C_2") (pintype "unspecified"))
      (node (ref "U32") (pin "15") (pinfunction "PA1_15") (pintype "unspecified"))
    )
    (net (code "6") (name "A2") (class "Default")
      (node (ref "R11") (pin "1") (pinfunction "1_1") (pintype "input"))
      (node (ref "U3") (pin "2") (pinfunction "C_2") (pintype "unspecified"))
      (node (ref "U32") (pin "16") (pinfunction "PA2_16") (pintype "unspecified"))
    )
    (net (code "7") (name "A3") (class "Default")
      (node (ref "R12") (pin "2") (pinfunction "2_2") (pintype "input"))
      (node (ref "U32") (pin "17") (pinfunction "PA3_17") (pintype "unspecified"))
      (node (ref "U4") (pin "2") (pinfunction "C_2") (pintype "unspecified"))
    )
    (net (code "8") (name "A4") (class "Default")
      (node (ref "R13") (pin "1") (pinfunction "1_1") (pintype "input"))
      (node (ref "U32") (pin "20") (pinfunction "PA4_20") (pintype "unspecified"))
      (node (ref "U5") (pin "2") (pinfunction "C_2") (pintype "unspecified"))
    )
    (net (code "9") (name "A5") (class "Default")
      (node (ref "R14") (pin "1") (pinfunction "1_1") (pintype "input"))
      (node (ref "U32") (pin "21") (pinfunction "PA5_21") (pintype "unspecified"))
      (node (ref "U6") (pin "2") (pinfunction "C_2") (pintype "unspecified"))
    )
    (net (code "10") (name "A6") (class "Default")
      (node (ref "R15") (pin "2") (pinfunction "2_2") (pintype "input"))
      (node (ref "U32") (pin "22") (pinfunction "PA6_22") (pintype "unspecified"))
      (node (ref "U7") (pin "2") (pinfunction "C_2") (pintype "unspecified"))
    )
    (net (code "11") (name "A7") (class "Default")
      (node (ref "R16") (pin "1") (pinfunction "1_1") (pintype "input"))
      (node (ref "U32") (pin "23") (pinfunction "PA7_23") (pintype "unspecified"))
      (node (ref "U8") (pin "2") (pinfunction "C_2") (pintype "unspecified"))
    )
    (net (code "12") (name "A8") (class "Default")
      (node (ref "R17") (pin "1") (pinfunction "1_1") (pintype "input"))
      (node (ref "U32") (pin "26") (pinfunction "PB0_26") (pintype "unspecified"))
      (node (ref "U9") (pin "2") (pinfunction "C_2") (pintype "unspecified"))
    )
    (net (code "13") (name "A9") (class "Default")
      (node (ref "R18") (pin "2") (pinfunction "2_2") (pintype "input"))
      (node (ref "U10") (pin "2") (pinfunction "C_2") (pintype "unspecified"))
      (node (ref "U32") (pin "27") (pinfunction "PB1_27") (pintype "unspecified"))
    )
    (net (code "14") (name "A10") (class "Default")
      (node (ref "R19") (pin "1") (pinfunction "1_1") (pintype "input"))
      (node (ref "U11") (pin "2") (pinfunction "C_2") (pintype "unspecified"))
      (node (ref "U32") (pin "8") (pinfunction "PC0_8") (pintype "unspecified"))
    )
    (net (code "15") (name "A11") (class "Default")
      (node (ref "R20") (pin "1") (pinfunction "1_1") (pintype "input"))
      (node (ref "U12") (pin "2") (pinfunction "C_2") (pintype "unspecified"))
      (node (ref "U32") (pin "9") (pinfunction "PC1_9") (pintype "unspecified"))
    )
    (net (code "16") (name "BOOT0") (class "Default")
      (node (ref "R48") (pin "1") (pinfunction "1_1") (pintype "input"))
      (node (ref "U32") (pin "60") (pinfunction "BOOT0_60") (pintype "unspecified"))
    )
    (net (code "17") (name "BOOT1") (class "Default")
      (node (ref "R49") (pin "2") (pinfunction "2_2") (pintype "input"))
      (node (ref "U32") (pin "28") (pinfunction "PB2_28") (pintype "unspecified"))
    )
    (net (code "18") (name "BTN1") (class "Default")
      (node (ref "U32") (pin "33") (pinfunction "PB12_33") (pintype "unspecified"))
      (node (ref "UP") (pin "1") (pinfunction "1_1") (pintype "input"))
    )
    (net (code "19") (name "BTN2") (class "Default")
      (node (ref "DOWN") (pin "1") (pinfunction "1_1") (pintype "input"))
      (node (ref "U32") (pin "34") (pinfunction "PB13_34") (pintype "unspecified"))
    )
    (net (code "20") (name "BTN3") (class "Default")
      (node (ref "MODE") (pin "1") (pinfunction "1_1") (pintype "input"))
      (node (ref "U32") (pin "35") (pinfunction "PB14_35") (pintype "unspecified"))
    )
    (net (code "21") (name "BTRX") (class "Default")
      (node (ref "HC-05") (pin "5") (pinfunction "5_5") (pintype "input"))
      (node (ref "U32") (pin "42") (pinfunction "PA9_42") (pintype "unspecified"))
    )
    (net (code "22") (name "BTTX") (class "Default")
      (node (ref "HC-05") (pin "4") (pinfunction "4_4") (pintype "input"))
      (node (ref "U32") (pin "43") (pinfunction "PA10_43") (pintype "unspecified"))
    )
    (net (code "23") (name "GND") (class "Default")
      (node (ref "7.4VBAT") (pin "2") (pinfunction "2_2") (pintype "input"))
      (node (ref "C10") (pin "1") (pinfunction "1_1") (pintype "input"))
      (node (ref "C11") (pin "2") (pinfunction "2_2") (pintype "input"))
      (node (ref "C12") (pin "2") (pinfunction "2_2") (pintype "input"))
      (node (ref "C13") (pin "2") (pinfunction "2_2") (pintype "input"))
      (node (ref "C14") (pin "2") (pinfunction "2_2") (pintype "input"))
      (node (ref "C15") (pin "1") (pinfunction "1_1") (pintype "input"))
      (node (ref "C16") (pin "1") (pinfunction "1_1") (pintype "input"))
      (node (ref "C17") (pin "1") (pinfunction "1_1") (pintype "input"))
      (node (ref "C18") (pin "1") (pinfunction "1_1") (pintype "input"))
      (node (ref "C2") (pin "1") (pinfunction "1_1") (pintype "unspecified"))
      (node (ref "C22") (pin "1") (pinfunction "1_1") (pintype "input"))
      (node (ref "C23") (pin "1") (pinfunction "1_1") (pintype "unspecified"))
      (node (ref "C24") (pin "1") (pinfunction "1_1") (pintype "input"))
      (node (ref "C25") (pin "1") (pinfunction "1_1") (pintype "input"))
      (node (ref "C26") (pin "1") (pinfunction "1_1") (pintype "input"))
      (node (ref "C6") (pin "1") (pinfunction "1_1") (pintype "input"))
      (node (ref "C7") (pin "1") (pinfunction "1_1") (pintype "input"))
      (node (ref "C9") (pin "1") (pinfunction "1_1") (pintype "input"))
      (node (ref "DEBUG") (pin "4") (pinfunction "4_4") (pintype "unspecified"))
      (node (ref "DOWN") (pin "3") (pinfunction "3_3") (pintype "input"))
      (node (ref "H1") (pin "5") (pinfunction "5_5") (pintype "unspecified"))
      (node (ref "H1") (pin "6") (pinfunction "6_6") (pintype "unspecified"))
      (node (ref "HC-05") (pin "3") (pinfunction "3_3") (pintype "input"))
      (node (ref "IR1") (pin "2") (pinfunction "GND_2") (pintype "input"))
      (node (ref "LCD") (pin "1") (pinfunction "1_1") (pintype "input"))
      (node (ref "MODE") (pin "3") (pinfunction "3_3") (pintype "input"))
      (node (ref "R53") (pin "1") (pinfunction "1_1") (pintype "input"))
      (node (ref "RST") (pin "1") (pinfunction "1_1") (pintype "input"))
      (node (ref "RST") (pin "2") (pinfunction "2_2") (pintype "input"))
      (node (ref "U1") (pin "1") (pinfunction "A_1") (pintype "unspecified"))
      (node (ref "U1") (pin "4") (pinfunction "EM_4") (pintype "unspecified"))
      (node (ref "U10") (pin "1") (pinfunction "A_1") (pintype "unspecified"))
      (node (ref "U10") (pin "4") (pinfunction "EM_4") (pintype "unspecified"))
      (node (ref "U11") (pin "1") (pinfunction "A_1") (pintype "unspecified"))
      (node (ref "U11") (pin "4") (pinfunction "EM_4") (pintype "unspecified"))
      (node (ref "U12") (pin "1") (pinfunction "A_1") (pintype "unspecified"))
      (node (ref "U12") (pin "4") (pinfunction "EM_4") (pintype "unspecified"))
      (node (ref "U16") (pin "5") (pinfunction "GND_5") (pintype "unspecified"))
      (node (ref "U16") (pin "6") (pinfunction "EH_6") (pintype "unspecified"))
      (node (ref "U16") (pin "7") (pinfunction "EH_7") (pintype "unspecified"))
      (node (ref "U16") (pin "8") (pinfunction "EH_8") (pintype "unspecified"))
      (node (ref "U16") (pin "9") (pinfunction "EH_9") (pintype "unspecified"))
      (node (ref "U2") (pin "1") (pinfunction "A_1") (pintype "unspecified"))
      (node (ref "U2") (pin "4") (pinfunction "EM_4") (pintype "unspecified"))
      (node (ref "U25") (pin "4") (pinfunction "GND_4") (pintype "unspecified"))
      (node (ref "U25") (pin "9") (pinfunction "PAD_9") (pintype "unspecified"))
      (node (ref "U26") (pin "4") (pinfunction "GND_4") (pintype "unspecified"))
      (node (ref "U26") (pin "9") (pinfunction "PAD_9") (pintype "unspecified"))
      (node (ref "U29") (pin "1") (pinfunction "GND_1") (pintype "input"))
      (node (ref "U3") (pin "1") (pinfunction "A_1") (pintype "unspecified"))
      (node (ref "U3") (pin "4") (pinfunction "EM_4") (pintype "unspecified"))
      (node (ref "U32") (pin "12") (pinfunction "VSSA_12") (pintype "unspecified"))
      (node (ref "U32") (pin "18") (pinfunction "VSS_4_18") (pintype "unspecified"))
      (node (ref "U32") (pin "31") (pinfunction "VSS_1_31") (pintype "unspecified"))
      (node (ref "U32") (pin "47") (pinfunction "VSS_2_47") (pintype "unspecified"))
      (node (ref "U32") (pin "63") (pinfunction "VSS_3_63") (pintype "unspecified"))
      (node (ref "U33") (pin "1") (pinfunction "GND_1") (pintype "unspecified"))
      (node (ref "U4") (pin "1") (pinfunction "A_1") (pintype "unspecified"))
      (node (ref "U4") (pin "4") (pinfunction "EM_4") (pintype "unspecified"))
      (node (ref "U5") (pin "1") (pinfunction "A_1") (pintype "unspecified"))
      (node (ref "U5") (pin "4") (pinfunction "EM_4") (pintype "unspecified"))
      (node (ref "U6") (pin "1") (pinfunction "A_1") (pintype "unspecified"))
      (node (ref "U6") (pin "4") (pinfunction "EM_4") (pintype "unspecified"))
      (node (ref "U7") (pin "1") (pinfunction "A_1") (pintype "unspecified"))
      (node (ref "U7") (pin "4") (pinfunction "EM_4") (pintype "unspecified"))
      (node (ref "U8") (pin "1") (pinfunction "A_1") (pintype "unspecified"))
      (node (ref "U8") (pin "4") (pinfunction "EM_4") (pintype "unspecified"))
      (node (ref "U9") (pin "1") (pinfunction "A_1") (pintype "unspecified"))
      (node (ref "U9") (pin "4") (pinfunction "EM_4") (pintype "unspecified"))
      (node (ref "UP") (pin "3") (pinfunction "3_3") (pintype "input"))
    )
    (net (code "24") (name "IRSIGNAL") (class "Default")
      (node (ref "IR1") (pin "1") (pinfunction "OUT_1") (pintype "input"))
      (node (ref "R76") (pin "1") (pinfunction "1_1") (pintype "unspecified"))
      (node (ref "U32") (pin "36") (pinfunction "PB15_36") (pintype "unspecified"))
    )
    (net (code "25") (name "M1P") (class "Default")
      (node (ref "U25") (pin "6") (pinfunction "PH_6") (pintype "unspecified"))
      (node (ref "U32") (pin "58") (pinfunction "PB6_58") (pintype "unspecified"))
    )
    (net (code "26") (name "M1S") (class "Default")
      (node (ref "U25") (pin "5") (pinfunction "EN_5") (pintype "unspecified"))
      (node (ref "U32") (pin "59") (pinfunction "PB7_59") (pintype "unspecified"))
    )
    (net (code "27") (name "M1SLEEP") (class "Default")
      (node (ref "R77") (pin "1") (pinfunction "1_1") (pintype "unspecified"))
      (node (ref "U25") (pin "7") (pinfunction "nSLEEP_7") (pintype "unspecified"))
      (node (ref "U32") (pin "56") (pinfunction "PB4_56") (pintype "unspecified"))
    )
    (net (code "28") (name "M2P") (class "Default")
      (node (ref "U26") (pin "6") (pinfunction "PH_6") (pintype "unspecified"))
      (node (ref "U32") (pin "61") (pinfunction "PB8_61") (pintype "unspecified"))
    )
    (net (code "29") (name "M2S") (class "Default")
      (node (ref "U26") (pin "5") (pinfunction "EN_5") (pintype "unspecified"))
      (node (ref "U32") (pin "62") (pinfunction "PB9_62") (pintype "unspecified"))
    )
    (net (code "30") (name "M2SLEEP") (class "Default")
      (node (ref "R78") (pin "1") (pinfunction "1_1") (pintype "unspecified"))
      (node (ref "U26") (pin "7") (pinfunction "nSLEEP_7") (pintype "unspecified"))
      (node (ref "U32") (pin "57") (pinfunction "PB5_57") (pintype "unspecified"))
    )
    (net (code "31") (name "Net-(7.4VBAT-Pad1)") (class "Default")
      (node (ref "7.4VBAT") (pin "1") (pinfunction "1_1") (pintype "input"))
      (node (ref "ON/OFF") (pin "2") (pinfunction "2_2") (pintype "input"))
    )
    (net (code "32") (name "Net-(DOWN-Pad2)") (class "Default")
      (node (ref "DOWN") (pin "2") (pinfunction "2_2") (pintype "input"))
      (node (ref "R62") (pin "2") (pinfunction "2_2") (pintype "unspecified"))
    )
    (net (code "33") (name "Net-(H1-Pad3)") (class "Default")
      (node (ref "H1") (pin "3") (pinfunction "3_3") (pintype "unspecified"))
      (node (ref "R48") (pin "2") (pinfunction "2_2") (pintype "input"))
    )
    (net (code "34") (name "Net-(H1-Pad4)") (class "Default")
      (node (ref "H1") (pin "4") (pinfunction "4_4") (pintype "unspecified"))
      (node (ref "R49") (pin "1") (pinfunction "1_1") (pintype "input"))
    )
    (net (code "35") (name "Net-(MODE-Pad2)") (class "Default")
      (node (ref "MODE") (pin "2") (pinfunction "2_2") (pintype "input"))
      (node (ref "R61") (pin "1") (pinfunction "1_1") (pintype "unspecified"))
    )
    (net (code "36") (name "Net-(R63-Pad1)") (class "Default")
      (node (ref "R63") (pin "1") (pinfunction "1_1") (pintype "unspecified"))
      (node (ref "UP") (pin "2") (pinfunction "2_2") (pintype "input"))
    )
    (net (code "37") (name "Net-(U1-COL)") (class "Default")
      (node (ref "R64") (pin "1") (pinfunction "1_1") (pintype "input"))
      (node (ref "U1") (pin "3") (pinfunction "COL_3") (pintype "unspecified"))
    )
    (net (code "38") (name "Net-(U2-COL)") (class "Default")
      (node (ref "R65") (pin "1") (pinfunction "1_1") (pintype "input"))
      (node (ref "U2") (pin "3") (pinfunction "COL_3") (pintype "unspecified"))
    )
    (net (code "39") (name "Net-(U3-COL)") (class "Default")
      (node (ref "R66") (pin "1") (pinfunction "1_1") (pintype "input"))
      (node (ref "U3") (pin "3") (pinfunction "COL_3") (pintype "unspecified"))
    )
    (net (code "40") (name "Net-(U4-COL)") (class "Default")
      (node (ref "R67") (pin "1") (pinfunction "1_1") (pintype "input"))
      (node (ref "U4") (pin "3") (pinfunction "COL_3") (pintype "unspecified"))
    )
    (net (code "41") (name "Net-(U5-COL)") (class "Default")
      (node (ref "R68") (pin "1") (pinfunction "1_1") (pintype "input"))
      (node (ref "U5") (pin "3") (pinfunction "COL_3") (pintype "unspecified"))
    )
    (net (code "42") (name "Net-(U6-COL)") (class "Default")
      (node (ref "R69") (pin "1") (pinfunction "1_1") (pintype "input"))
      (node (ref "U6") (pin "3") (pinfunction "COL_3") (pintype "unspecified"))
    )
    (net (code "43") (name "Net-(U7-COL)") (class "Default")
      (node (ref "R70") (pin "1") (pinfunction "1_1") (pintype "input"))
      (node (ref "U7") (pin "3") (pinfunction "COL_3") (pintype "unspecified"))
    )
    (net (code "44") (name "Net-(U8-COL)") (class "Default")
      (node (ref "R71") (pin "1") (pinfunction "1_1") (pintype "input"))
      (node (ref "U8") (pin "3") (pinfunction "COL_3") (pintype "unspecified"))
    )
    (net (code "45") (name "Net-(U9-COL)") (class "Default")
      (node (ref "R72") (pin "1") (pinfunction "1_1") (pintype "input"))
      (node (ref "U9") (pin "3") (pinfunction "COL_3") (pintype "unspecified"))
    )
    (net (code "46") (name "Net-(U10-COL)") (class "Default")
      (node (ref "R73") (pin "1") (pinfunction "1_1") (pintype "input"))
      (node (ref "U10") (pin "3") (pinfunction "COL_3") (pintype "unspecified"))
    )
    (net (code "47") (name "Net-(U11-COL)") (class "Default")
      (node (ref "R74") (pin "1") (pinfunction "1_1") (pintype "input"))
      (node (ref "U11") (pin "3") (pinfunction "COL_3") (pintype "unspecified"))
    )
    (net (code "48") (name "Net-(U12-COL)") (class "Default")
      (node (ref "R75") (pin "1") (pinfunction "1_1") (pintype "input"))
      (node (ref "U12") (pin "3") (pinfunction "COL_3") (pintype "unspecified"))
    )
    (net (code "49") (name "Net-(U16-D+)") (class "Default")
      (node (ref "R51") (pin "2") (pinfunction "2_2") (pintype "input"))
      (node (ref "U16") (pin "3") (pinfunction "D+_3") (pintype "unspecified"))
    )
    (net (code "50") (name "Net-(U16-D-)") (class "Default")
      (node (ref "R50") (pin "2") (pinfunction "2_2") (pintype "input"))
      (node (ref "U16") (pin "2") (pinfunction "D-_2") (pintype "unspecified"))
    )
    (net (code "51") (name "Net-(U17-K)") (class "Default")
      (node (ref "R53") (pin "2") (pinfunction "2_2") (pintype "input"))
      (node (ref "U17") (pin "1") (pinfunction "K_1") (pintype "unspecified"))
    )
    (net (code "52") (name "Net-(U18-K)") (class "Default")
      (node (ref "R54") (pin "2") (pinfunction "2_2") (pintype "input"))
      (node (ref "U18") (pin "1") (pinfunction "K_1") (pintype "unspecified"))
    )
    (net (code "53") (name "Net-(U25-OUT1)") (class "Default")
      (node (ref "MOTOR1") (pin "2") (pinfunction "2_2") (pintype "input"))
      (node (ref "U25") (pin "2") (pinfunction "OUT1_2") (pintype "unspecified"))
    )
    (net (code "54") (name "Net-(U25-OUT2)") (class "Default")
      (node (ref "MOTOR1") (pin "1") (pinfunction "1_1") (pintype "input"))
      (node (ref "U25") (pin "3") (pinfunction "OUT2_3") (pintype "unspecified"))
    )
    (net (code "55") (name "Net-(U26-OUT1)") (class "Default")
      (node (ref "MOTOR2") (pin "2") (pinfunction "2_2") (pintype "input"))
      (node (ref "U26") (pin "2") (pinfunction "OUT1_2") (pintype "unspecified"))
    )
    (net (code "56") (name "Net-(U26-OUT2)") (class "Default")
      (node (ref "MOTOR2") (pin "1") (pinfunction "1_1") (pintype "input"))
      (node (ref "U26") (pin "3") (pinfunction "OUT2_3") (pintype "unspecified"))
    )
    (net (code "57") (name "OSC32IN") (class "Default")
      (node (ref "C13") (pin "1") (pinfunction "1_1") (pintype "input"))
      (node (ref "U32") (pin "3") (pinfunction "PC14-SOC32_IN_3") (pintype "unspecified"))
      (node (ref "X4") (pin "2") (pinfunction "OSC2_2") (pintype "input"))
    )
    (net (code "58") (name "OSC32OUT") (class "Default")
      (node (ref "C14") (pin "1") (pinfunction "1_1") (pintype "input"))
      (node (ref "U32") (pin "4") (pinfunction "PC15-SOC32_OUT_4") (pintype "unspecified"))
      (node (ref "X4") (pin "1") (pinfunction "OSC1_1") (pintype "input"))
    )
    (net (code "59") (name "OSCIN") (class "Default")
      (node (ref "C12") (pin "1") (pinfunction "1_1") (pintype "input"))
      (node (ref "R25") (pin "2") (pinfunction "2_2") (pintype "input"))
      (node (ref "U32") (pin "5") (pinfunction "PD0OSC_IN_5") (pintype "unspecified"))
      (node (ref "X3") (pin "1") (pinfunction "OSC1_1") (pintype "input"))
    )
    (net (code "60") (name "OSCOUT") (class "Default")
      (node (ref "C11") (pin "1") (pinfunction "1_1") (pintype "input"))
      (node (ref "R25") (pin "1") (pinfunction "1_1") (pintype "input"))
      (node (ref "U32") (pin "6") (pinfunction "PD1OSC_OUT_6") (pintype "unspecified"))
      (node (ref "X3") (pin "2") (pinfunction "OSC2_2") (pintype "input"))
    )
    (net (code "61") (name "PA11") (class "Default")
      (node (ref "R50") (pin "1") (pinfunction "1_1") (pintype "input"))
      (node (ref "U32") (pin "44") (pinfunction "PA11_44") (pintype "unspecified"))
    )
    (net (code "62") (name "PA12") (class "Default")
      (node (ref "R51") (pin "1") (pinfunction "1_1") (pintype "input"))
      (node (ref "R52") (pin "1") (pinfunction "1_1") (pintype "input"))
      (node (ref "U32") (pin "45") (pinfunction "PA12_45") (pintype "unspecified"))
    )
    (net (code "63") (name "PC13") (class "Default")
      (node (ref "R54") (pin "1") (pinfunction "1_1") (pintype "input"))
      (node (ref "U32") (pin "2") (pinfunction "PC13-TAMPER-RTC_2") (pintype "unspecified"))
    )
    (net (code "64") (name "RESET") (class "Default")
      (node (ref "C2") (pin "2") (pinfunction "2_2") (pintype "unspecified"))
      (node (ref "R47") (pin "1") (pinfunction "1_1") (pintype "unspecified"))
      (node (ref "RST") (pin "3") (pinfunction "3_3") (pintype "input"))
      (node (ref "RST") (pin "4") (pinfunction "4_4") (pintype "input"))
      (node (ref "U32") (pin "7") (pinfunction "NRST_7") (pintype "unspecified"))
    )
    (net (code "65") (name "SCL") (class "Default")
      (node (ref "LCD") (pin "3") (pinfunction "3_3") (pintype "input"))
      (node (ref "U32") (pin "29") (pinfunction "PB10_29") (pintype "unspecified"))
    )
    (net (code "66") (name "SDA") (class "Default")
      (node (ref "LCD") (pin "4") (pinfunction "4_4") (pintype "input"))
      (node (ref "U32") (pin "30") (pinfunction "PB11_30") (pintype "unspecified"))
    )
    (net (code "67") (name "SWDCLK") (class "Default")
      (node (ref "DEBUG") (pin "3") (pinfunction "3_3") (pintype "unspecified"))
      (node (ref "U32") (pin "49") (pinfunction "PA14_49") (pintype "unspecified"))
    )
    (net (code "68") (name "SWDIO") (class "Default")
      (node (ref "DEBUG") (pin "2") (pinfunction "2_2") (pintype "unspecified"))
      (node (ref "U32") (pin "46") (pinfunction "PA13_46") (pintype "unspecified"))
    )
    (net (code "69") (name "unconnected-(DOWN-Pad4)") (class "Default")
      (node (ref "DOWN") (pin "4") (pinfunction "4_4") (pintype "input"))
    )
    (net (code "70") (name "unconnected-(HC-05-Pad1)") (class "Default")
      (node (ref "HC-05") (pin "1") (pinfunction "1_1") (pintype "input"))
    )
    (net (code "71") (name "unconnected-(HC-05-Pad6)") (class "Default")
      (node (ref "HC-05") (pin "6") (pinfunction "6_6") (pintype "input"))
    )
    (net (code "72") (name "unconnected-(MODE-Pad4)") (class "Default")
      (node (ref "MODE") (pin "4") (pinfunction "4_4") (pintype "input"))
    )
    (net (code "73") (name "unconnected-(ON/OFF-Pad1)") (class "Default")
      (node (ref "ON/OFF") (pin "1") (pinfunction "1_1") (pintype "input"))
    )
    (net (code "74") (name "unconnected-(U16-ID-Pad4)") (class "Default")
      (node (ref "U16") (pin "4") (pinfunction "ID_4") (pintype "unspecified"))
    )
    (net (code "75") (name "unconnected-(U32-PA8-Pad41)") (class "Default")
      (node (ref "U32") (pin "41") (pinfunction "PA8_41") (pintype "unspecified"))
    )
    (net (code "76") (name "unconnected-(U32-PA15-Pad50)") (class "Default")
      (node (ref "U32") (pin "50") (pinfunction "PA15_50") (pintype "unspecified"))
    )
    (net (code "77") (name "unconnected-(U32-PB3-Pad55)") (class "Default")
      (node (ref "U32") (pin "55") (pinfunction "PB3_55") (pintype "unspecified"))
    )
    (net (code "78") (name "unconnected-(U32-PC2-Pad10)") (class "Default")
      (node (ref "U32") (pin "10") (pinfunction "PC2_10") (pintype "unspecified"))
    )
    (net (code "79") (name "unconnected-(U32-PC3-Pad11)") (class "Default")
      (node (ref "U32") (pin "11") (pinfunction "PC3_11") (pintype "unspecified"))
    )
    (net (code "80") (name "unconnected-(U32-PC4-Pad24)") (class "Default")
      (node (ref "U32") (pin "24") (pinfunction "PC4_24") (pintype "unspecified"))
    )
    (net (code "81") (name "unconnected-(U32-PC5-Pad25)") (class "Default")
      (node (ref "U32") (pin "25") (pinfunction "PC5_25") (pintype "unspecified"))
    )
    (net (code "82") (name "unconnected-(U32-PC6-Pad37)") (class "Default")
      (node (ref "U32") (pin "37") (pinfunction "PC6_37") (pintype "unspecified"))
    )
    (net (code "83") (name "unconnected-(U32-PC7-Pad38)") (class "Default")
      (node (ref "U32") (pin "38") (pinfunction "PC7_38") (pintype "unspecified"))
    )
    (net (code "84") (name "unconnected-(U32-PC8-Pad39)") (class "Default")
      (node (ref "U32") (pin "39") (pinfunction "PC8_39") (pintype "unspecified"))
    )
    (net (code "85") (name "unconnected-(U32-PC9-Pad40)") (class "Default")
      (node (ref "U32") (pin "40") (pinfunction "PC9_40") (pintype "unspecified"))
    )
    (net (code "86") (name "unconnected-(U32-PC10-Pad51)") (class "Default")
      (node (ref "U32") (pin "51") (pinfunction "PC10_51") (pintype "unspecified"))
    )
    (net (code "87") (name "unconnected-(U32-PC11-Pad52)") (class "Default")
      (node (ref "U32") (pin "52") (pinfunction "PC11_52") (pintype "unspecified"))
    )
    (net (code "88") (name "unconnected-(U32-PC12-Pad53)") (class "Default")
      (node (ref "U32") (pin "53") (pinfunction "PC12_53") (pintype "unspecified"))
    )
    (net (code "89") (name "unconnected-(U32-PD2-Pad54)") (class "Default")
      (node (ref "U32") (pin "54") (pinfunction "PD2_54") (pintype "unspecified"))
    )
    (net (code "90") (name "unconnected-(UP-Pad4)") (class "Default")
      (node (ref "UP") (pin "4") (pinfunction "4_4") (pintype "input"))
    )
  )
)
